# C64_Combi_PSU.net
KiCad netlist of a schematic drawn in EAGLE
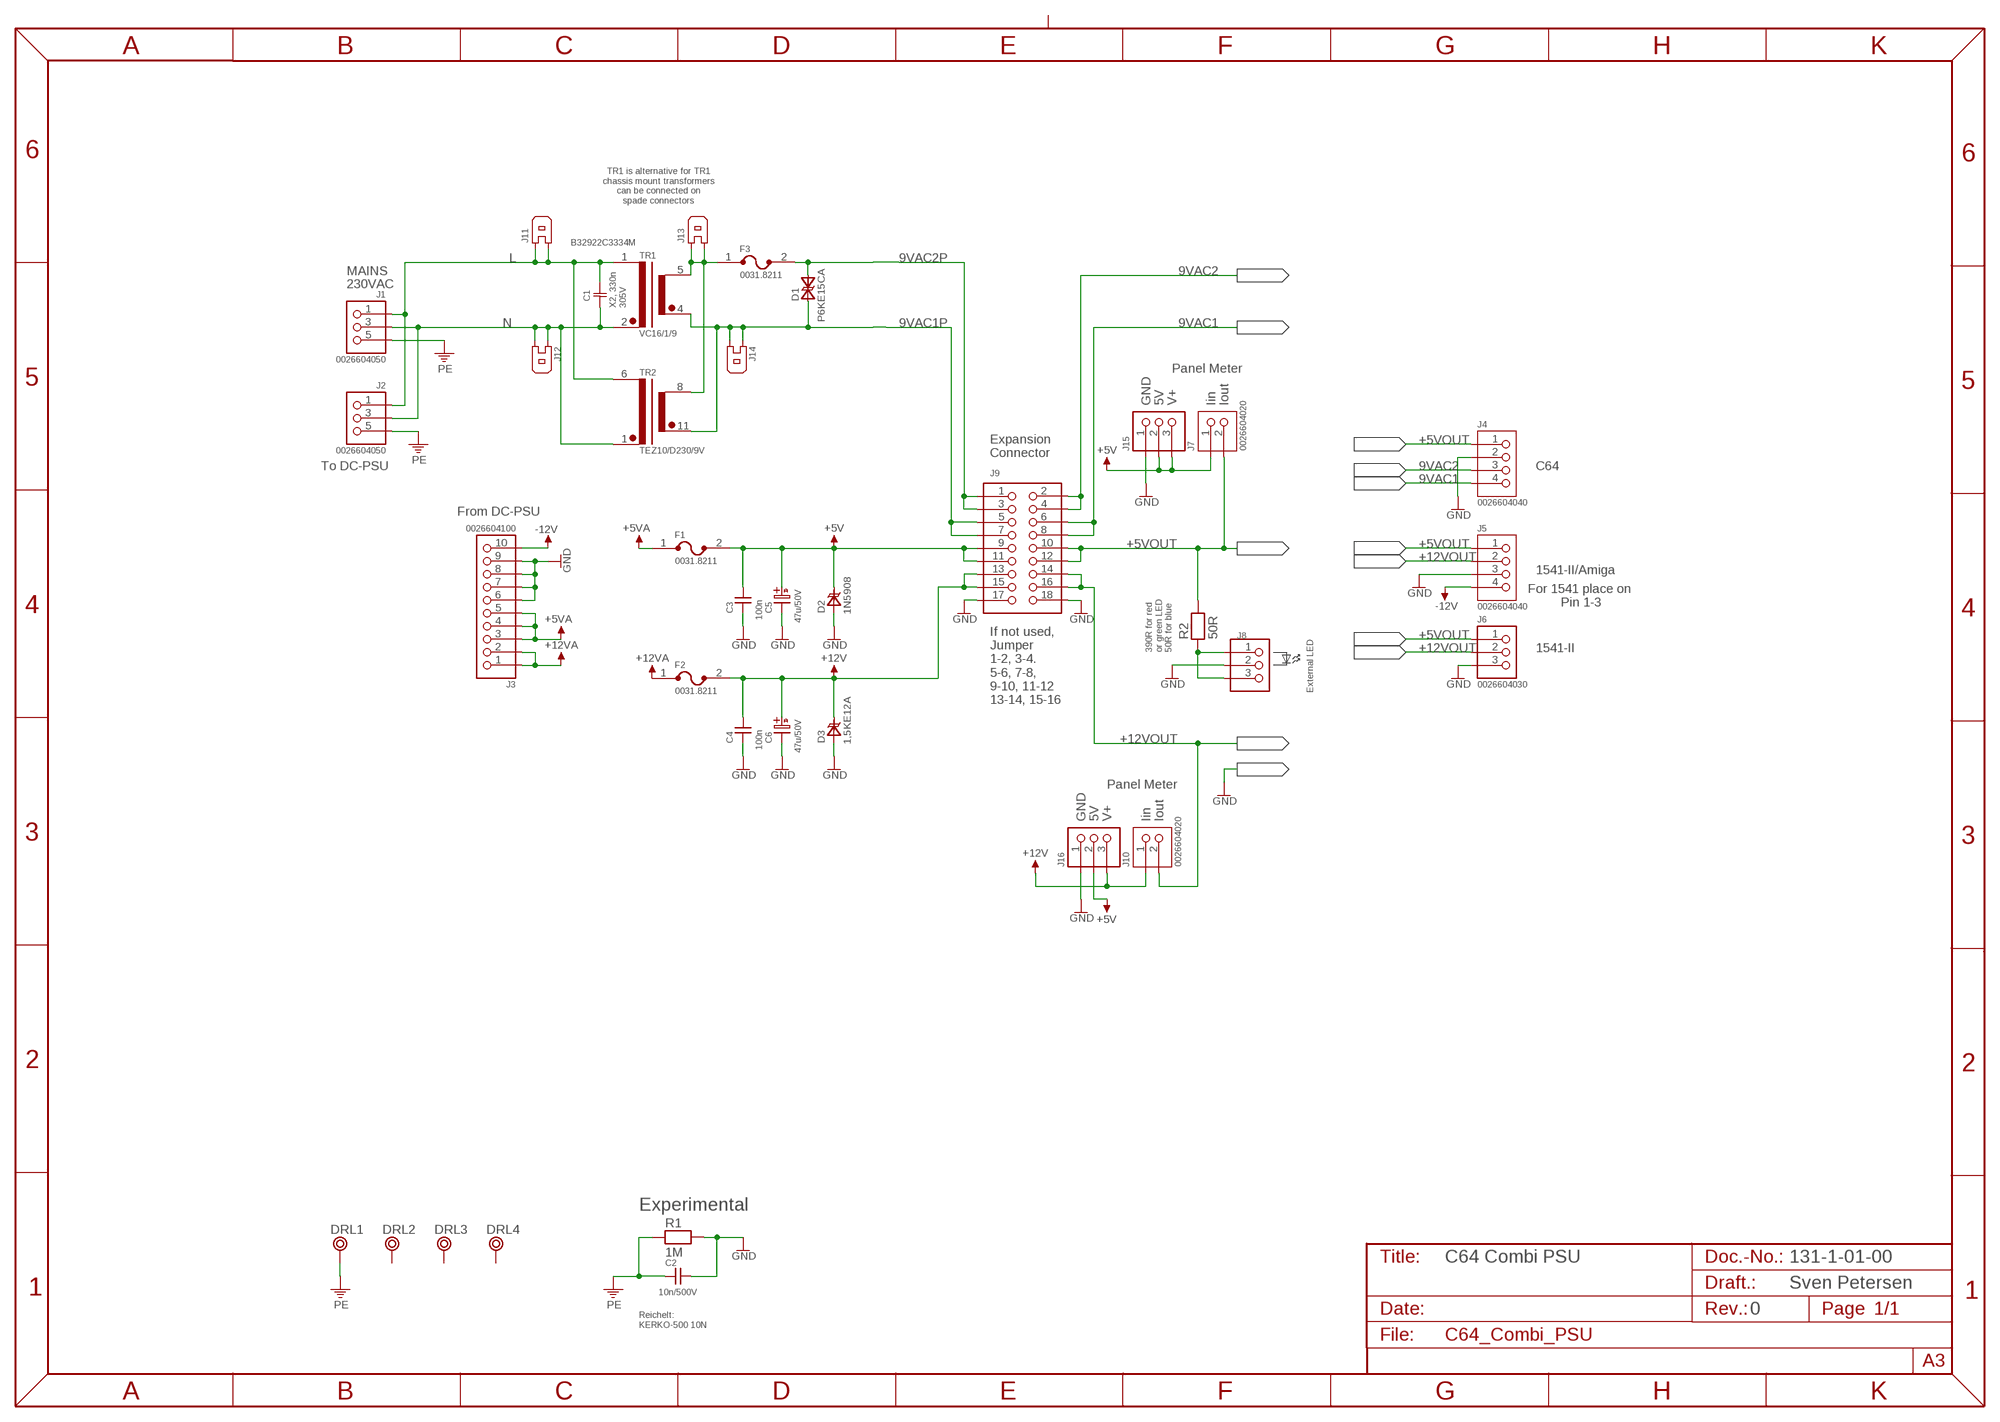
[diagram p0: schematic, sheet 1]

(export (version "E")
  (design (tool "Eeschema 10.0.6"))
  (components
    (comp (ref "C1")
      (value "B32922C3334M")
      (footprint "eagle-import:C-18X8-RM15")
      (libsource (lib "eagle-import") (part "X2--RM15-18X8"))
    )
    (comp (ref "C2")
      (value "10n/500V")
      (footprint "eagle-import:C-5")
      (libsource (lib "eagle-import") (part "CAP02"))
    )
    (comp (ref "C3")
      (value "100n")
      (footprint "eagle-import:C-2,5")
      (libsource (lib "eagle-import") (part "CAP01"))
    )
    (comp (ref "C4")
      (value "100n")
      (footprint "eagle-import:C-2,5")
      (libsource (lib "eagle-import") (part "CAP01"))
    )
    (comp (ref "C5")
      (value "47u/50V")
      (footprint "eagle-import:C07_2,5")
      (libsource (lib "eagle-import") (part "C07/2,5"))
    )
    (comp (ref "C6")
      (value "47u/50V")
      (footprint "eagle-import:C07_2,5")
      (libsource (lib "eagle-import") (part "C07/2,5"))
    )
    (comp (ref "D1")
      (value "P6KE15CA")
      (footprint "eagle-import:CB417NP")
      (libsource (lib "eagle-import") (part "P6KE15CA"))
    )
    (comp (ref "D2")
      (value "1N5908")
      (footprint "eagle-import:CB429")
      (libsource (lib "eagle-import") (part "1N5908"))
    )
    (comp (ref "D3")
      (value "1,5KE12A")
      (footprint "eagle-import:DO-201")
      (libsource (lib "eagle-import") (part "1,5KE12A"))
    )
    (comp (ref "DRL1")
      (value "BOHR3,5")
      (footprint "eagle-import:BOHR3,5")
      (libsource (lib "eagle-import") (part "BOHR3,5"))
    )
    (comp (ref "DRL2")
      (value "BOHR3,5")
      (footprint "eagle-import:BOHR3,5")
      (libsource (lib "eagle-import") (part "BOHR3,5"))
    )
    (comp (ref "DRL3")
      (value "BOHR3,5")
      (footprint "eagle-import:BOHR3,5")
      (libsource (lib "eagle-import") (part "BOHR3,5"))
    )
    (comp (ref "DRL4")
      (value "BOHR3,5")
      (footprint "eagle-import:BOHR3,5")
      (libsource (lib "eagle-import") (part "BOHR3,5"))
    )
    (comp (ref "F1")
      (value "0031.8211")
      (footprint "eagle-import:0031.8211")
      (libsource (lib "eagle-import") (part "0031.8211"))
    )
    (comp (ref "F2")
      (value "0031.8211")
      (footprint "eagle-import:0031.8211")
      (libsource (lib "eagle-import") (part "0031.8211"))
    )
    (comp (ref "F3")
      (value "0031.8211")
      (footprint "eagle-import:0031.8211")
      (libsource (lib "eagle-import") (part "0031.8211"))
    )
    (comp (ref "J1")
      (value "0026604050")
      (footprint "eagle-import:SPOX_3.96_5P3")
      (libsource (lib "eagle-import") (part "0026604050MOD"))
    )
    (comp (ref "J2")
      (value "0026604050")
      (footprint "eagle-import:SPOX_3.96_5P3")
      (libsource (lib "eagle-import") (part "0026604050MOD"))
    )
    (comp (ref "J3")
      (value "0026604100")
      (footprint "eagle-import:SPOX_3.96_10P")
      (libsource (lib "eagle-import") (part "0026604100"))
    )
    (comp (ref "J4")
      (value "0026604040")
      (footprint "eagle-import:SPOX_3.96_4P")
      (libsource (lib "eagle-import") (part "0026604040"))
    )
    (comp (ref "J5")
      (value "0026604040")
      (footprint "eagle-import:SPOX_3.96_4P")
      (libsource (lib "eagle-import") (part "0026604040"))
    )
    (comp (ref "J6")
      (value "0026604030")
      (footprint "eagle-import:SPOX_3.96_3P")
      (libsource (lib "eagle-import") (part "0026604030"))
    )
    (comp (ref "J7")
      (value "0026604020")
      (footprint "eagle-import:SPOX_3.96_2P")
      (libsource (lib "eagle-import") (part "0026604020"))
    )
    (comp (ref "J8")
      (value "PINHD-1X3")
      (footprint "eagle-import:1X03")
      (libsource (lib "eagle-import") (part "PINHD-1X3"))
    )
    (comp (ref "J9")
      (value "PINHD-2X9")
      (footprint "eagle-import:2X09")
      (libsource (lib "eagle-import") (part "PINHD-2X9"))
    )
    (comp (ref "J10")
      (value "0026604020")
      (footprint "eagle-import:SPOX_3.96_2P")
      (libsource (lib "eagle-import") (part "0026604020"))
    )
    (comp (ref "J11")
      (value "FLA6,3")
      (footprint "eagle-import:FLA6,3")
      (libsource (lib "eagle-import") (part "FLA6,3"))
    )
    (comp (ref "J12")
      (value "FLA6,3")
      (footprint "eagle-import:FLA6,3")
      (libsource (lib "eagle-import") (part "FLA6,3"))
    )
    (comp (ref "J13")
      (value "FLA6,3")
      (footprint "eagle-import:FLA6,3")
      (libsource (lib "eagle-import") (part "FLA6,3"))
    )
    (comp (ref "J14")
      (value "FLA6,3")
      (footprint "eagle-import:FLA6,3")
      (libsource (lib "eagle-import") (part "FLA6,3"))
    )
    (comp (ref "J15")
      (value "6410-3P")
      (footprint "eagle-import:6410-3P")
      (libsource (lib "eagle-import") (part "6410-3P"))
    )
    (comp (ref "J16")
      (value "6410-3P")
      (footprint "eagle-import:6410-3P")
      (libsource (lib "eagle-import") (part "6410-3P"))
    )
    (comp (ref "R1")
      (value "1M")
      (footprint "eagle-import:R-10")
      (libsource (lib "eagle-import") (part "RES04"))
    )
    (comp (ref "R2")
      (value "50R")
      (footprint "eagle-import:R-10")
      (libsource (lib "eagle-import") (part "RES04"))
    )
    (comp (ref "TR1")
      (value "VC16/1/9")
      (footprint "eagle-import:VC16_1_9")
      (libsource (lib "eagle-import") (part "VC16/1/9"))
    )
    (comp (ref "TR2")
      (value "TEZ10/D230/9V")
      (footprint "eagle-import:TEZ10")
      (libsource (lib "eagle-import") (part "TEZ10/D230/9V"))
    )
  )
  (nets
    (net (code "1") (name "+5V") (class "Default")
      (node (ref "C3") (pin "2") (pinfunction "2_2") (pintype "passive"))
      (node (ref "C5") (pin "A") (pinfunction "+_A") (pintype "passive"))
      (node (ref "D2") (pin "K") (pinfunction "K_K") (pintype "passive"))
      (node (ref "F1") (pin "2") (pinfunction "2_2") (pintype "passive"))
      (node (ref "J15") (pin "2") (pinfunction "2_2") (pintype "passive"))
      (node (ref "J15") (pin "3") (pinfunction "3_3") (pintype "passive"))
      (node (ref "J16") (pin "2") (pinfunction "2_2") (pintype "passive"))
      (node (ref "J7") (pin "1") (pinfunction "1_1") (pintype "passive"))
      (node (ref "J9") (pin "11") (pinfunction "11_11") (pintype "passive"))
      (node (ref "J9") (pin "9") (pinfunction "9_9") (pintype "passive"))
    )
    (net (code "2") (name "+5VA") (class "Default")
      (node (ref "F1") (pin "1") (pinfunction "1_1") (pintype "passive"))
      (node (ref "J3") (pin "3") (pinfunction "3_3") (pintype "passive"))
      (node (ref "J3") (pin "4") (pinfunction "4_4") (pintype "passive"))
      (node (ref "J3") (pin "5") (pinfunction "5_5") (pintype "passive"))
    )
    (net (code "3") (name "+12V") (class "Default")
      (node (ref "C4") (pin "2") (pinfunction "2_2") (pintype "passive"))
      (node (ref "C6") (pin "A") (pinfunction "+_A") (pintype "passive"))
      (node (ref "D3") (pin "K") (pinfunction "K_K") (pintype "passive"))
      (node (ref "F2") (pin "2") (pinfunction "2_2") (pintype "passive"))
      (node (ref "J10") (pin "1") (pinfunction "1_1") (pintype "passive"))
      (node (ref "J16") (pin "3") (pinfunction "3_3") (pintype "passive"))
      (node (ref "J9") (pin "13") (pinfunction "13_13") (pintype "passive"))
      (node (ref "J9") (pin "15") (pinfunction "15_15") (pintype "passive"))
    )
    (net (code "4") (name "+12VA") (class "Default")
      (node (ref "F2") (pin "1") (pinfunction "1_1") (pintype "passive"))
      (node (ref "J3") (pin "1") (pinfunction "1_1") (pintype "passive"))
      (node (ref "J3") (pin "2") (pinfunction "2_2") (pintype "passive"))
    )
    (net (code "5") (name "-12V") (class "Default")
      (node (ref "J3") (pin "10") (pinfunction "10_10") (pintype "passive"))
      (node (ref "J5") (pin "4") (pinfunction "4_4") (pintype "passive"))
    )
    (net (code "6") (name "/+5VOUT") (class "Default")
      (node (ref "J4") (pin "1") (pinfunction "1_1") (pintype "passive"))
      (node (ref "J5") (pin "1") (pinfunction "1_1") (pintype "passive"))
      (node (ref "J6") (pin "1") (pinfunction "1_1") (pintype "passive"))
      (node (ref "J7") (pin "2") (pinfunction "2_2") (pintype "passive"))
      (node (ref "J9") (pin "10") (pinfunction "10_10") (pintype "passive"))
      (node (ref "J9") (pin "12") (pinfunction "12_12") (pintype "passive"))
      (node (ref "R2") (pin "2") (pinfunction "2_2") (pintype "passive"))
    )
    (net (code "7") (name "/+12VOUT") (class "Default")
      (node (ref "J10") (pin "2") (pinfunction "2_2") (pintype "passive"))
      (node (ref "J5") (pin "2") (pinfunction "2_2") (pintype "passive"))
      (node (ref "J6") (pin "2") (pinfunction "2_2") (pintype "passive"))
      (node (ref "J9") (pin "14") (pinfunction "14_14") (pintype "passive"))
      (node (ref "J9") (pin "16") (pinfunction "16_16") (pintype "passive"))
    )
    (net (code "8") (name "/9VAC1") (class "Default")
      (node (ref "J4") (pin "4") (pinfunction "4_4") (pintype "passive"))
      (node (ref "J9") (pin "6") (pinfunction "6_6") (pintype "passive"))
      (node (ref "J9") (pin "8") (pinfunction "8_8") (pintype "passive"))
    )
    (net (code "9") (name "/9VAC1P") (class "Default")
      (node (ref "D1") (pin "A") (pinfunction "A1_A") (pintype "passive"))
      (node (ref "J14") (pin "1") (pinfunction "1_1") (pintype "passive"))
      (node (ref "J14") (pin "2") (pinfunction "2_2") (pintype "passive"))
      (node (ref "J9") (pin "5") (pinfunction "5_5") (pintype "passive"))
      (node (ref "J9") (pin "7") (pinfunction "7_7") (pintype "passive"))
      (node (ref "TR1") (pin "4") (pinfunction "SEC12_4") (pintype "passive"))
      (node (ref "TR2") (pin "11") (pinfunction "SEC12_11") (pintype "passive"))
    )
    (net (code "10") (name "/9VAC2") (class "Default")
      (node (ref "J4") (pin "3") (pinfunction "3_3") (pintype "passive"))
      (node (ref "J9") (pin "2") (pinfunction "2_2") (pintype "passive"))
      (node (ref "J9") (pin "4") (pinfunction "4_4") (pintype "passive"))
    )
    (net (code "11") (name "/9VAC2P") (class "Default")
      (node (ref "D1") (pin "K") (pinfunction "A2_K") (pintype "passive"))
      (node (ref "F3") (pin "2") (pinfunction "2_2") (pintype "passive"))
      (node (ref "J9") (pin "1") (pinfunction "1_1") (pintype "passive"))
      (node (ref "J9") (pin "3") (pinfunction "3_3") (pintype "passive"))
    )
    (net (code "12") (name "/L") (class "Default")
      (node (ref "C1") (pin "2") (pinfunction "2_2") (pintype "passive"))
      (node (ref "J1") (pin "1") (pinfunction "1_1") (pintype "passive"))
      (node (ref "J11") (pin "1") (pinfunction "1_1") (pintype "passive"))
      (node (ref "J11") (pin "2") (pinfunction "2_2") (pintype "passive"))
      (node (ref "J2") (pin "1") (pinfunction "1_1") (pintype "passive"))
      (node (ref "TR1") (pin "1") (pinfunction "PRI1_1") (pintype "passive"))
      (node (ref "TR2") (pin "6") (pinfunction "PRI1_6") (pintype "passive"))
    )
    (net (code "13") (name "/N") (class "Default")
      (node (ref "C1") (pin "1") (pinfunction "1_1") (pintype "passive"))
      (node (ref "J1") (pin "3") (pinfunction "2_3") (pintype "passive"))
      (node (ref "J12") (pin "1") (pinfunction "1_1") (pintype "passive"))
      (node (ref "J12") (pin "2") (pinfunction "2_2") (pintype "passive"))
      (node (ref "J2") (pin "3") (pinfunction "2_3") (pintype "passive"))
      (node (ref "TR1") (pin "2") (pinfunction "PRI2_2") (pintype "passive"))
      (node (ref "TR2") (pin "1") (pinfunction "PRI2_1") (pintype "passive"))
    )
    (net (code "14") (name "GND") (class "Default")
      (node (ref "C2") (pin "2") (pinfunction "2_2") (pintype "passive"))
      (node (ref "C3") (pin "1") (pinfunction "1_1") (pintype "passive"))
      (node (ref "C4") (pin "1") (pinfunction "1_1") (pintype "passive"))
      (node (ref "C5") (pin "K") (pinfunction "-_K") (pintype "passive"))
      (node (ref "C6") (pin "K") (pinfunction "-_K") (pintype "passive"))
      (node (ref "D2") (pin "A") (pinfunction "A_A") (pintype "passive"))
      (node (ref "D3") (pin "A") (pinfunction "A_A") (pintype "passive"))
      (node (ref "J15") (pin "1") (pinfunction "1_1") (pintype "passive"))
      (node (ref "J16") (pin "1") (pinfunction "1_1") (pintype "passive"))
      (node (ref "J3") (pin "6") (pinfunction "6_6") (pintype "passive"))
      (node (ref "J3") (pin "7") (pinfunction "7_7") (pintype "passive"))
      (node (ref "J3") (pin "8") (pinfunction "8_8") (pintype "passive"))
      (node (ref "J3") (pin "9") (pinfunction "9_9") (pintype "passive"))
      (node (ref "J4") (pin "2") (pinfunction "2_2") (pintype "passive"))
      (node (ref "J5") (pin "3") (pinfunction "3_3") (pintype "passive"))
      (node (ref "J6") (pin "3") (pinfunction "3_3") (pintype "passive"))
      (node (ref "J8") (pin "2") (pinfunction "2_2") (pintype "passive"))
      (node (ref "J9") (pin "17") (pinfunction "17_17") (pintype "passive"))
      (node (ref "J9") (pin "18") (pinfunction "18_18") (pintype "passive"))
      (node (ref "R1") (pin "2") (pinfunction "2_2") (pintype "passive"))
    )
    (net (code "15") (name "Net-(J8-Pad1)") (class "Default")
      (node (ref "J8") (pin "1") (pinfunction "1_1") (pintype "passive"))
      (node (ref "J8") (pin "3") (pinfunction "3_3") (pintype "passive"))
      (node (ref "R2") (pin "1") (pinfunction "1_1") (pintype "passive"))
    )
    (net (code "16") (name "Net-(TR1-SEC11)") (class "Default")
      (node (ref "F3") (pin "1") (pinfunction "1_1") (pintype "passive"))
      (node (ref "J13") (pin "1") (pinfunction "1_1") (pintype "passive"))
      (node (ref "J13") (pin "2") (pinfunction "2_2") (pintype "passive"))
      (node (ref "TR1") (pin "5") (pinfunction "SEC11_5") (pintype "passive"))
      (node (ref "TR2") (pin "8") (pinfunction "SEC11_8") (pintype "passive"))
    )
    (net (code "17") (name "PE") (class "Default")
      (node (ref "C2") (pin "1") (pinfunction "1_1") (pintype "passive"))
      (node (ref "DRL1") (pin "P$1") (pinfunction "P$1_P$1") (pintype "passive"))
      (node (ref "J1") (pin "5") (pinfunction "3_5") (pintype "passive"))
      (node (ref "J2") (pin "5") (pinfunction "3_5") (pintype "passive"))
      (node (ref "R1") (pin "1") (pinfunction "1_1") (pintype "passive"))
    )
    (net (code "18") (name "unconnected-(DRL2-PadP$1)") (class "Default")
      (node (ref "DRL2") (pin "P$1") (pinfunction "P$1_P$1") (pintype "passive"))
    )
    (net (code "19") (name "unconnected-(DRL3-PadP$1)") (class "Default")
      (node (ref "DRL3") (pin "P$1") (pinfunction "P$1_P$1") (pintype "passive"))
    )
    (net (code "20") (name "unconnected-(DRL4-PadP$1)") (class "Default")
      (node (ref "DRL4") (pin "P$1") (pinfunction "P$1_P$1") (pintype "passive"))
    )
  )
)
